# module_tester-v01.net
KiCad netlist of a schematic drawn in EAGLE
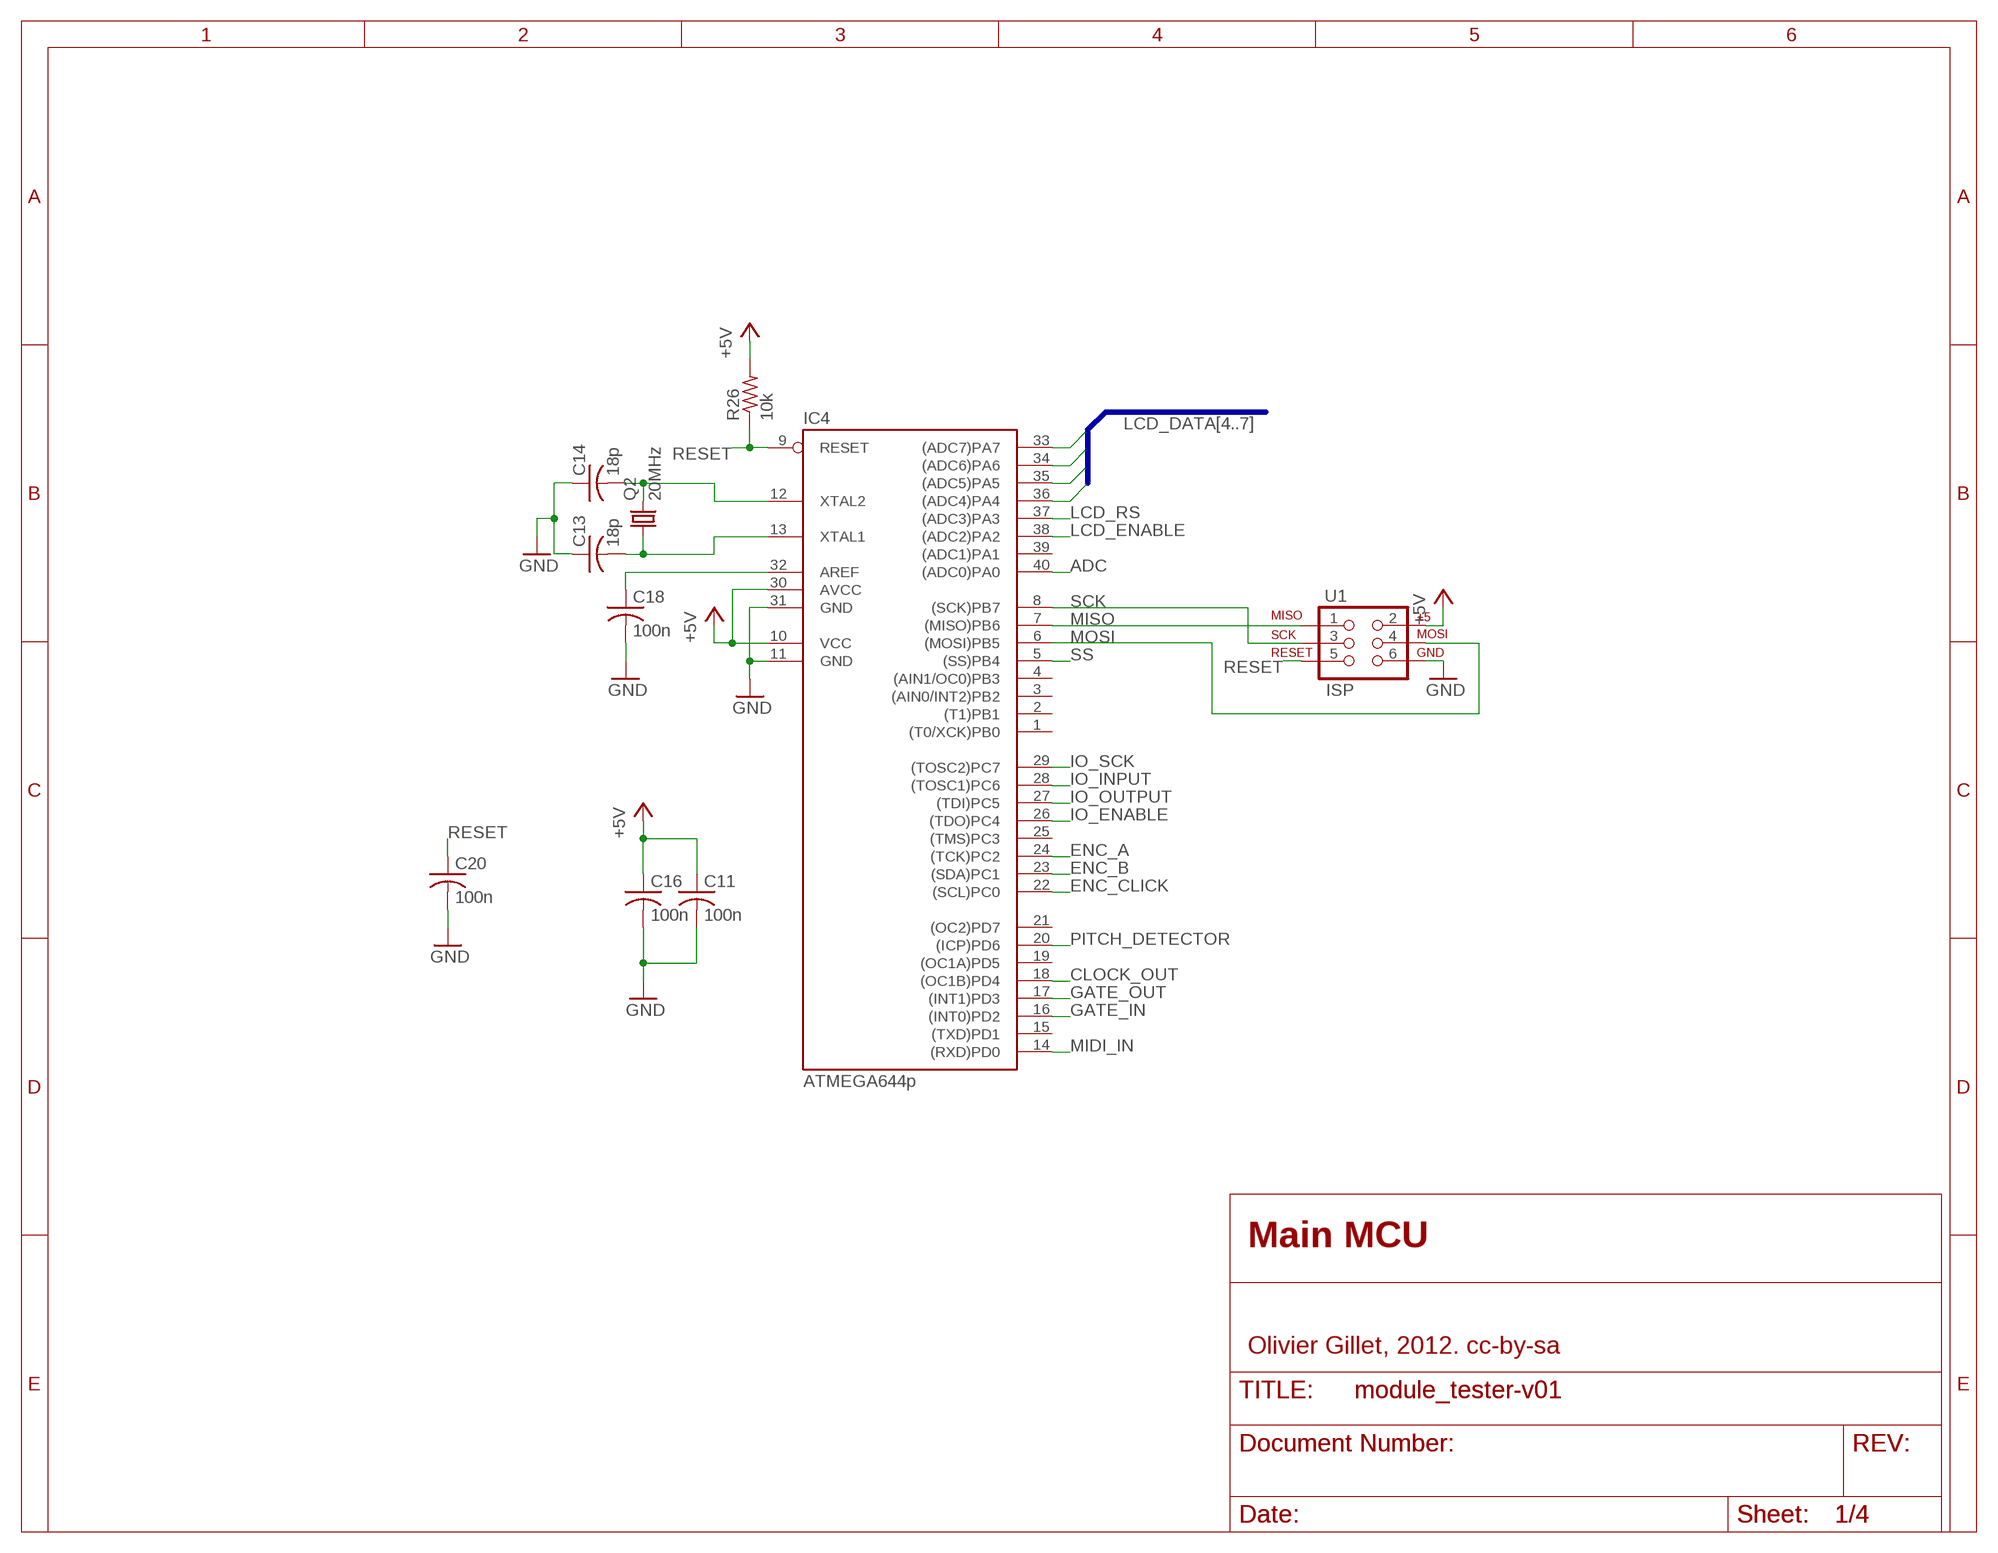
[diagram p0: schematic, sheet 1]
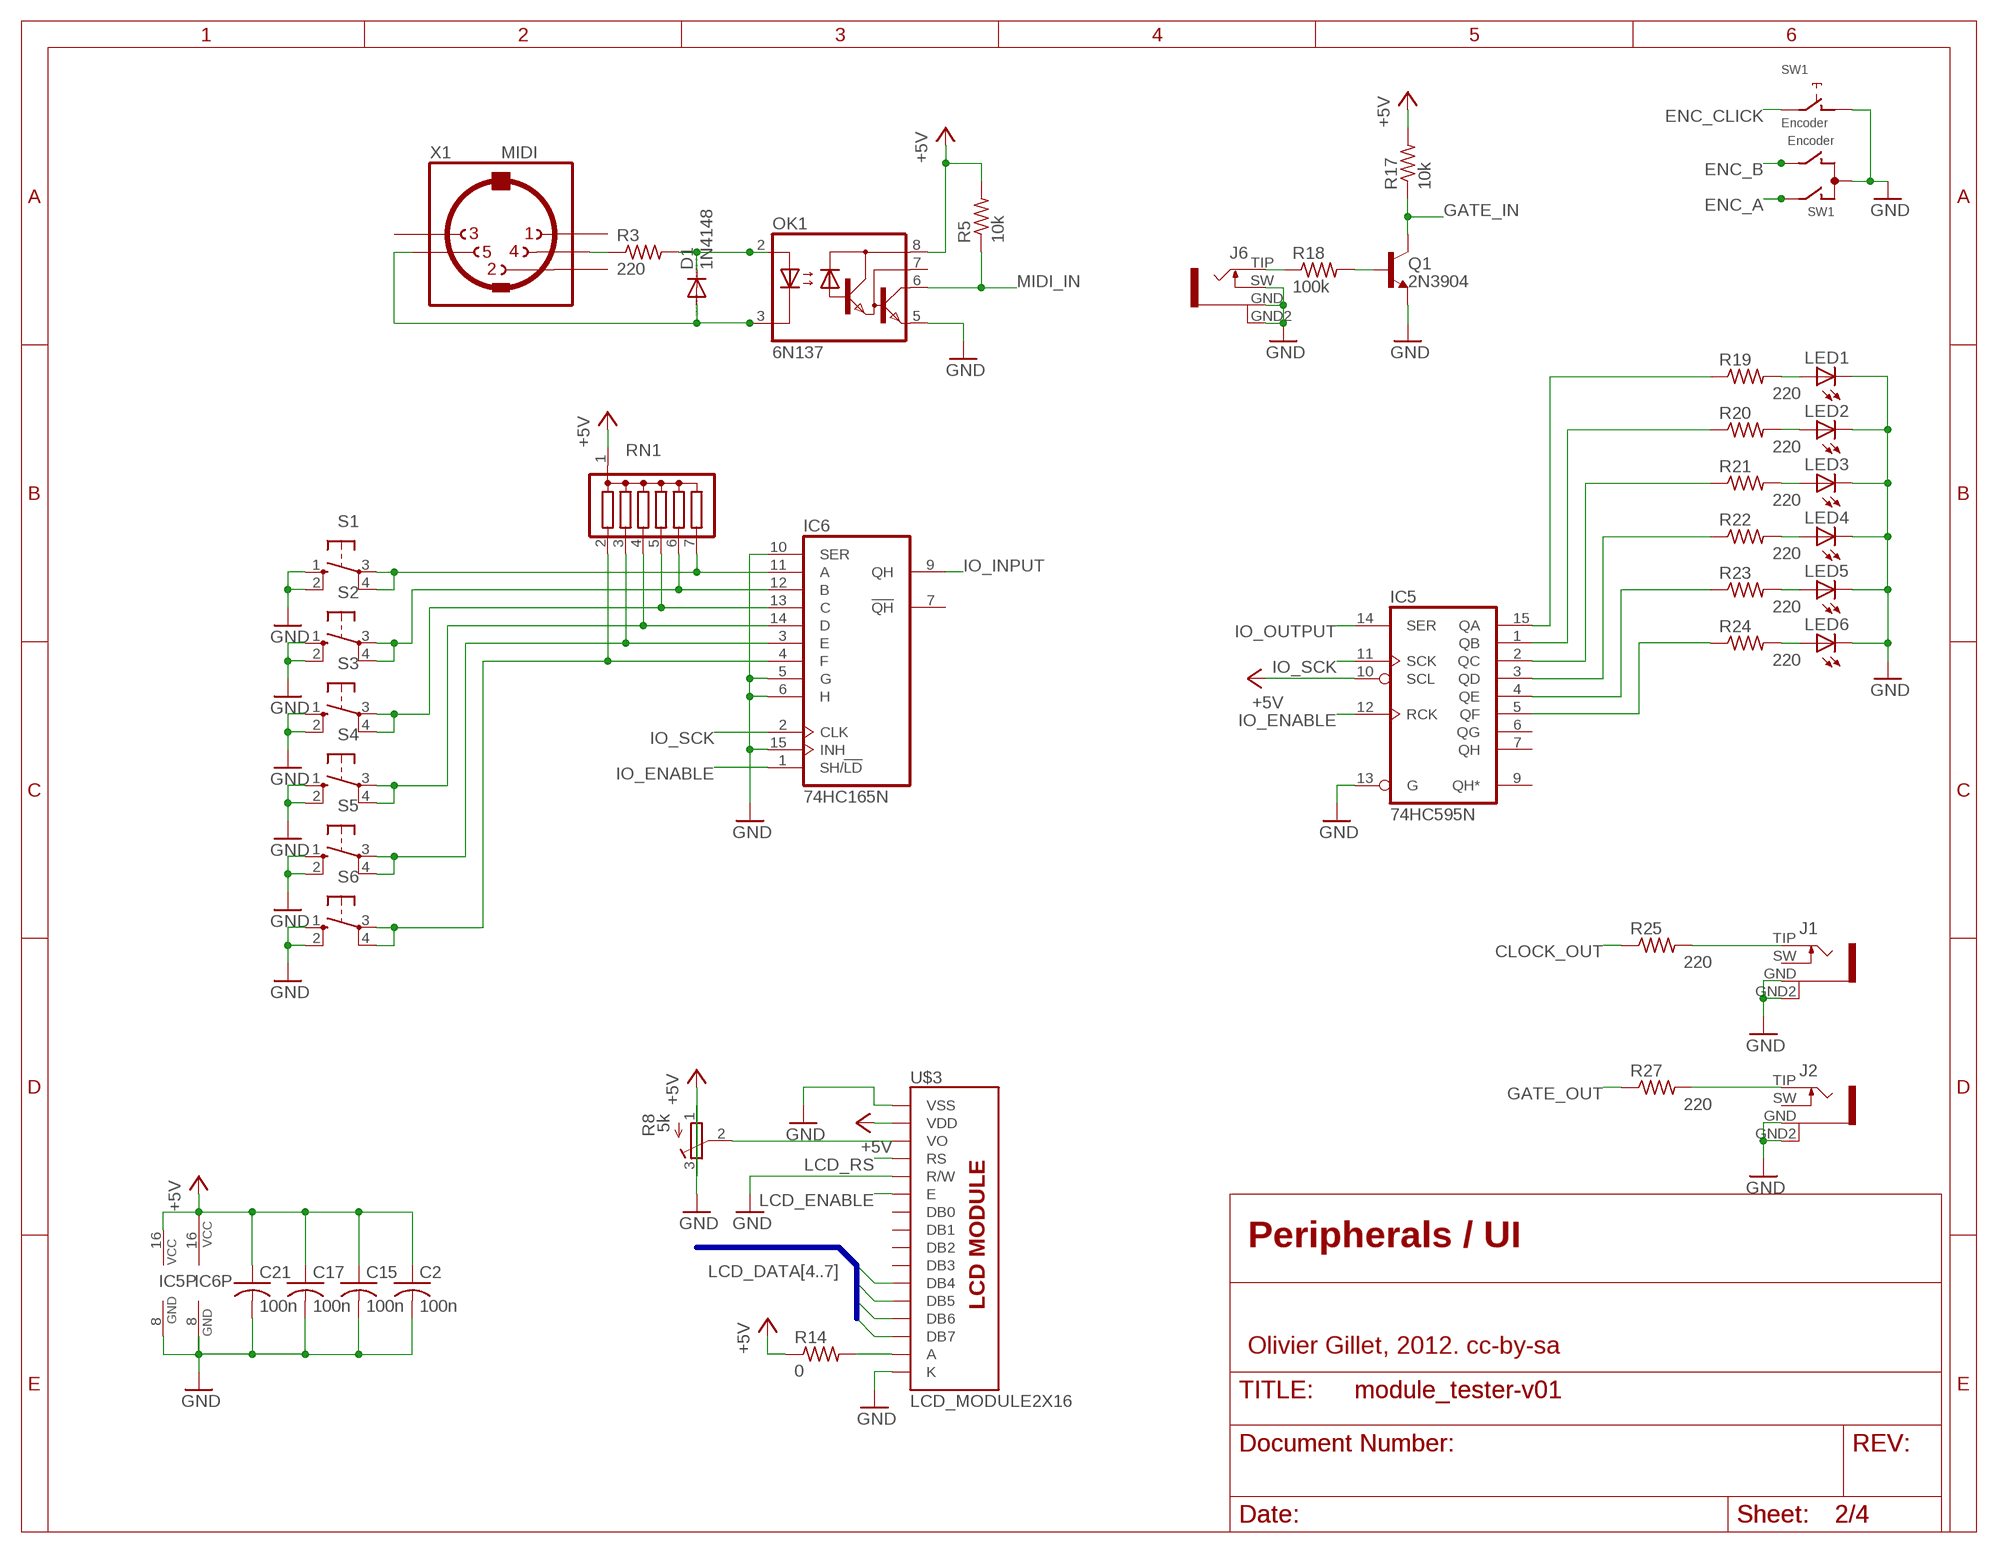
[diagram p1: schematic, sheet 2]
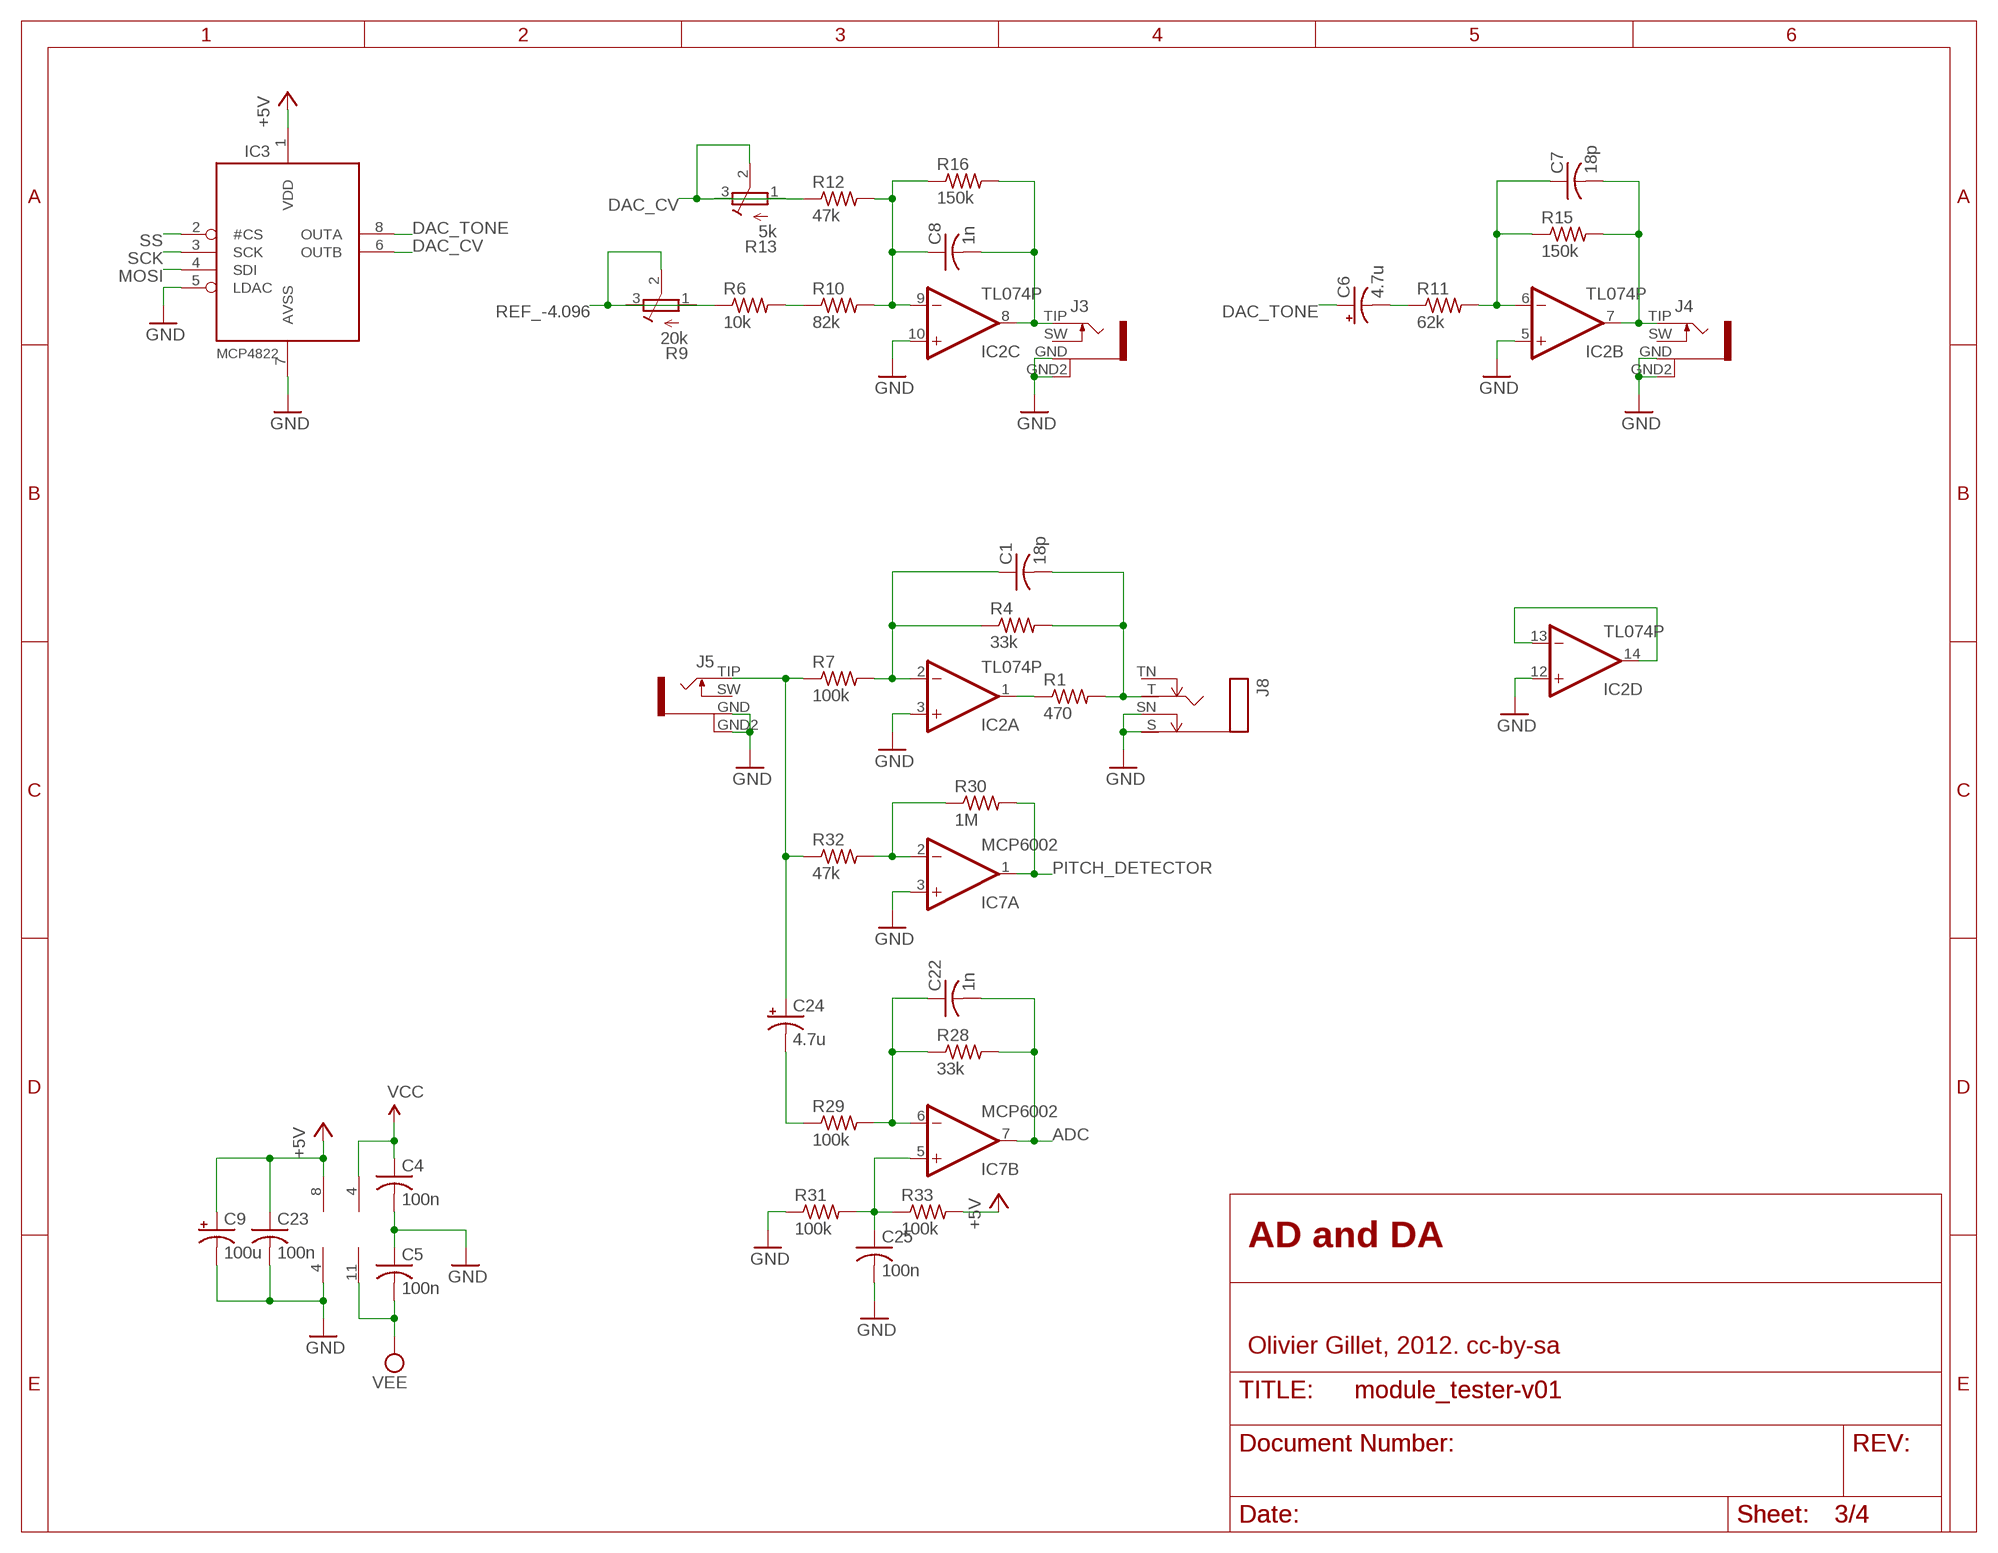
[diagram p2: schematic, sheet 3]
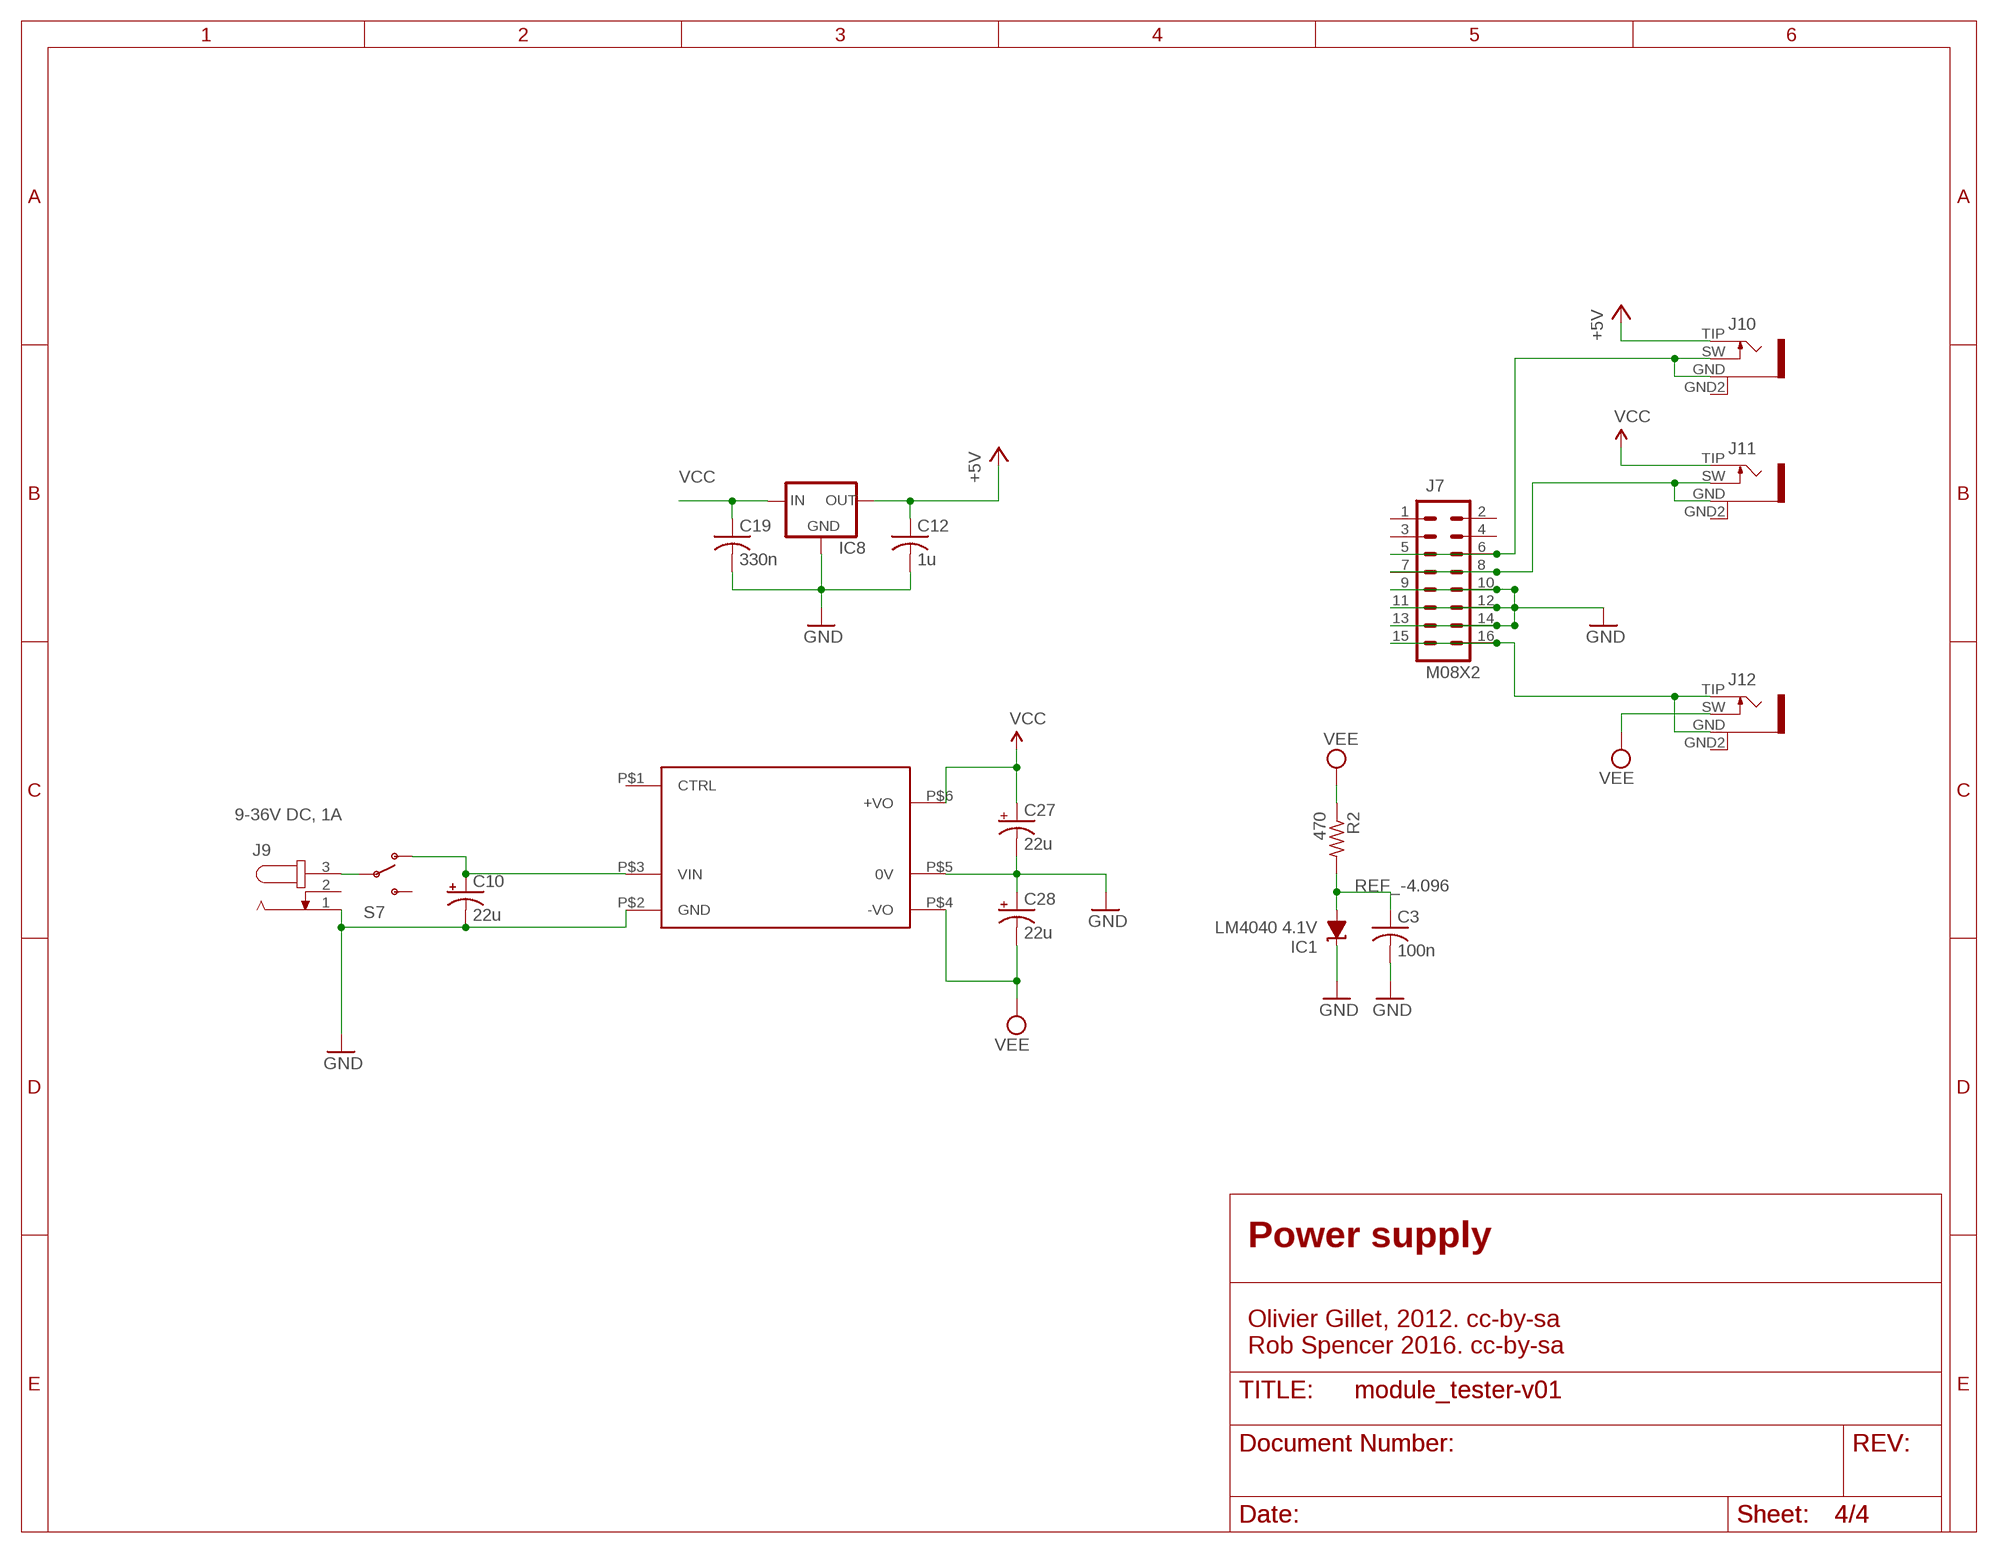
[diagram p3: schematic, sheet 4]

(export (version "E")
  (design (tool "Eeschema 10.0.6"))
  (components
    (comp (ref "C3")
      (value "100n")
      (footprint "eagle-import:C025-025X050")
      (libsource (lib "eagle-import") (part "C-US025-025X050"))
    )
    (comp (ref "C10")
      (value "22u")
      (footprint "eagle-import:E2,5-7")
      (libsource (lib "eagle-import") (part "CPOL-USE2.5-7"))
    )
    (comp (ref "C12")
      (value "1u")
      (footprint "eagle-import:C025-025X050")
      (libsource (lib "eagle-import") (part "C-US025-025X050"))
    )
    (comp (ref "C19")
      (value "330n")
      (footprint "eagle-import:C025-025X050")
      (libsource (lib "eagle-import") (part "C-US025-025X050"))
    )
    (comp (ref "C27")
      (value "22u")
      (footprint "eagle-import:E2,5-7")
      (libsource (lib "eagle-import") (part "CPOL-USE2.5-7"))
    )
    (comp (ref "C28")
      (value "22u")
      (footprint "eagle-import:E2,5-7")
      (libsource (lib "eagle-import") (part "CPOL-USE2.5-7"))
    )
    (comp (ref "IC1")
      (value "LM4040 4.1V")
      (footprint "eagle-import:LP_O-PBCY-W3")
      (fields (field (name "MPN") "LM4041C12ILP"))
      (libsource (lib "eagle-import") (part "LM4041LPC12"))
    )
    (comp (ref "IC8")
      (value "V_REG_78XX-TO-220")
      (footprint "eagle-import:TO-220-ALT")
      (libsource (lib "eagle-import") (part "V_REG_78XX-TO-220"))
    )
    (comp (ref "J7")
      (value "M08X2")
      (footprint "eagle-import:2X8")
      (libsource (lib "eagle-import") (part "M08X2"))
    )
    (comp (ref "J9")
      (value "JACK-PLUG2")
      (footprint "eagle-import:SPC4078_BIG_HOLES")
      (libsource (lib "eagle-import") (part "JACK-PLUG2"))
    )
    (comp (ref "J10")
      (value "PJ301WQP")
      (footprint "eagle-import:WQP_PJ_301BM")
      (libsource (lib "eagle-import") (part "PJ301WQP"))
    )
    (comp (ref "J11")
      (value "PJ301WQP")
      (footprint "eagle-import:WQP_PJ_301BM")
      (libsource (lib "eagle-import") (part "PJ301WQP"))
    )
    (comp (ref "J12")
      (value "PJ301WQP")
      (footprint "eagle-import:WQP_PJ_301BM")
      (libsource (lib "eagle-import") (part "PJ301WQP"))
    )
    (comp (ref "R2")
      (value "470")
      (footprint "eagle-import:0204_7")
      (libsource (lib "eagle-import") (part "resistor_R-US_0204/7"))
    )
    (comp (ref "S7")
      (value "SWITCH-SPDTPTH")
      (footprint "eagle-import:SWITCH-SPDT")
      (libsource (lib "eagle-import") (part "SWITCH-SPDTPTH"))
    )
    (comp (ref "U$10")
      (value "URA241XLD-20WR3")
      (footprint "eagle-import:URA241XLD-20WR3")
      (libsource (lib "eagle-import") (part "URA241XLD-20WR3"))
    )
    (comp (ref "C1")
      (value "18p")
      (footprint "eagle-import:C025-025X050")
      (libsource (lib "eagle-import") (part "C-US025-025X050"))
    )
    (comp (ref "C4")
      (value "100n")
      (footprint "eagle-import:C025-025X050")
      (libsource (lib "eagle-import") (part "C-US025-025X050"))
    )
    (comp (ref "C5")
      (value "100n")
      (footprint "eagle-import:C025-025X050")
      (libsource (lib "eagle-import") (part "C-US025-025X050"))
    )
    (comp (ref "C6")
      (value "4.7u")
      (footprint "eagle-import:E2,5-6")
      (libsource (lib "eagle-import") (part "CPOL-USE2.5-6"))
    )
    (comp (ref "C7")
      (value "18p")
      (footprint "eagle-import:C025-025X050")
      (libsource (lib "eagle-import") (part "C-US025-025X050"))
    )
    (comp (ref "C8")
      (value "1n")
      (footprint "eagle-import:C025-025X050")
      (libsource (lib "eagle-import") (part "C-US025-025X050"))
    )
    (comp (ref "C9")
      (value "100u")
      (footprint "eagle-import:E2,5-7")
      (libsource (lib "eagle-import") (part "CPOL-USE2.5-7"))
    )
    (comp (ref "C22")
      (value "1n")
      (footprint "eagle-import:C025-025X050")
      (libsource (lib "eagle-import") (part "C-US025-025X050"))
    )
    (comp (ref "C23")
      (value "100n")
      (footprint "eagle-import:C025-025X050")
      (libsource (lib "eagle-import") (part "C-US025-025X050"))
    )
    (comp (ref "C24")
      (value "4.7u")
      (footprint "eagle-import:E2,5-6")
      (libsource (lib "eagle-import") (part "CPOL-USE2.5-6"))
    )
    (comp (ref "C25")
      (value "100n")
      (footprint "eagle-import:C025-025X050")
      (libsource (lib "eagle-import") (part "C-US025-025X050"))
    )
    (comp (ref "IC2")
      (value "TL074P")
      (footprint "eagle-import:DIL14")
      (libsource (lib "eagle-import") (part "TL074P"))
    )
    (comp (ref "IC3")
      (value "MCP4822")
      (footprint "eagle-import:DIL08")
      (libsource (lib "eagle-import") (part "MCP4822"))
    )
    (comp (ref "IC7")
      (value "MCP6002")
      (footprint "eagle-import:DIL08")
      (libsource (lib "eagle-import") (part "TL072P"))
    )
    (comp (ref "J3")
      (value "PJ301WQP")
      (footprint "eagle-import:WQP_PJ_301BM")
      (libsource (lib "eagle-import") (part "PJ301WQP"))
    )
    (comp (ref "J4")
      (value "PJ301WQP")
      (footprint "eagle-import:WQP_PJ_301BM")
      (libsource (lib "eagle-import") (part "PJ301WQP"))
    )
    (comp (ref "J5")
      (value "PJ301WQP")
      (footprint "eagle-import:WQP_PJ_301BM")
      (libsource (lib "eagle-import") (part "PJ301WQP"))
    )
    (comp (ref "J8")
      (value "MONOSWSLIM")
      (footprint "eagle-import:NRJ4HF")
      (libsource (lib "eagle-import") (part "MONOSWSLIM"))
    )
    (comp (ref "R1")
      (value "470")
      (footprint "eagle-import:0204_7")
      (libsource (lib "eagle-import") (part "R-US_0204/7"))
    )
    (comp (ref "R4")
      (value "33k")
      (footprint "eagle-import:0204_7")
      (libsource (lib "eagle-import") (part "R-US_0204/7"))
    )
    (comp (ref "R6")
      (value "10k")
      (footprint "eagle-import:0204_7")
      (libsource (lib "eagle-import") (part "R-US_0204/7"))
    )
    (comp (ref "R7")
      (value "100k")
      (footprint "eagle-import:0204_7")
      (libsource (lib "eagle-import") (part "R-US_0204/7"))
    )
    (comp (ref "R9")
      (value "20k")
      (footprint "eagle-import:RTRIM3296W")
      (libsource (lib "eagle-import") (part "R-TRIMM3296W"))
    )
    (comp (ref "R10")
      (value "82k")
      (footprint "eagle-import:0204_7")
      (libsource (lib "eagle-import") (part "R-US_0204/7"))
    )
    (comp (ref "R11")
      (value "62k")
      (footprint "eagle-import:0204_7")
      (libsource (lib "eagle-import") (part "R-US_0204/7"))
    )
    (comp (ref "R12")
      (value "47k")
      (footprint "eagle-import:0204_7")
      (libsource (lib "eagle-import") (part "R-US_0204/7"))
    )
    (comp (ref "R13")
      (value "5k")
      (footprint "eagle-import:RTRIM3296W")
      (libsource (lib "eagle-import") (part "R-TRIMM3296W"))
    )
    (comp (ref "R15")
      (value "150k")
      (footprint "eagle-import:0204_7")
      (libsource (lib "eagle-import") (part "R-US_0204/7"))
    )
    (comp (ref "R16")
      (value "150k")
      (footprint "eagle-import:0204_7")
      (libsource (lib "eagle-import") (part "R-US_0204/7"))
    )
    (comp (ref "R28")
      (value "33k")
      (footprint "eagle-import:0204_7")
      (libsource (lib "eagle-import") (part "R-US_0204/7"))
    )
    (comp (ref "R29")
      (value "100k")
      (footprint "eagle-import:0204_7")
      (libsource (lib "eagle-import") (part "R-US_0204/7"))
    )
    (comp (ref "R30")
      (value "1M")
      (footprint "eagle-import:0204_7")
      (libsource (lib "eagle-import") (part "R-US_0204/7"))
    )
    (comp (ref "R31")
      (value "100k")
      (footprint "eagle-import:0204_7")
      (libsource (lib "eagle-import") (part "R-US_0204/7"))
    )
    (comp (ref "R32")
      (value "47k")
      (footprint "eagle-import:0204_7")
      (libsource (lib "eagle-import") (part "R-US_0204/7"))
    )
    (comp (ref "R33")
      (value "100k")
      (footprint "eagle-import:0204_7")
      (libsource (lib "eagle-import") (part "R-US_0204/7"))
    )
    (comp (ref "C11")
      (value "100n")
      (footprint "eagle-import:C025-025X050")
      (libsource (lib "eagle-import") (part "C-US025-025X050"))
    )
    (comp (ref "C13")
      (value "18p")
      (footprint "eagle-import:C025-025X050")
      (libsource (lib "eagle-import") (part "C-US025-025X050"))
    )
    (comp (ref "C14")
      (value "18p")
      (footprint "eagle-import:C025-025X050")
      (libsource (lib "eagle-import") (part "C-US025-025X050"))
    )
    (comp (ref "C16")
      (value "100n")
      (footprint "eagle-import:C025-025X050")
      (libsource (lib "eagle-import") (part "C-US025-025X050"))
    )
    (comp (ref "C18")
      (value "100n")
      (footprint "eagle-import:C025-025X050")
      (libsource (lib "eagle-import") (part "C-US025-025X050"))
    )
    (comp (ref "C20")
      (value "100n")
      (footprint "eagle-import:C025-025X050")
      (libsource (lib "eagle-import") (part "C-US025-025X050"))
    )
    (comp (ref "IC4")
      (value "ATMEGA644p")
      (footprint "eagle-import:DIL40")
      (fields (field (name "MPN") "ATMEGA16-16PU"))
      (libsource (lib "eagle-import") (part "MEGA16-P"))
    )
    (comp (ref "Q2")
      (value "20MHz")
      (footprint "eagle-import:HC49U-V")
      (libsource (lib "eagle-import") (part "CRYSTALHC49U-V"))
    )
    (comp (ref "R26")
      (value "10k")
      (footprint "eagle-import:0204_7")
      (libsource (lib "eagle-import") (part "R-US_0204/7"))
    )
    (comp (ref "U1")
      (value "ISP")
      (footprint "eagle-import:2X3")
      (libsource (lib "eagle-import") (part "AVR_SPI_PRG_6PTH"))
    )
    (comp (ref "C2")
      (value "100n")
      (footprint "eagle-import:C025-025X050")
      (libsource (lib "eagle-import") (part "C-US025-025X050"))
    )
    (comp (ref "C15")
      (value "100n")
      (footprint "eagle-import:C025-025X050")
      (libsource (lib "eagle-import") (part "C-US025-025X050"))
    )
    (comp (ref "C17")
      (value "100n")
      (footprint "eagle-import:C025-025X050")
      (libsource (lib "eagle-import") (part "C-US025-025X050"))
    )
    (comp (ref "C21")
      (value "100n")
      (footprint "eagle-import:C025-025X050")
      (libsource (lib "eagle-import") (part "C-US025-025X050"))
    )
    (comp (ref "D1")
      (value "1N4148")
      (footprint "eagle-import:D-5")
      (libsource (lib "eagle-import") (part "DIODE-D-5"))
    )
    (comp (ref "IC5")
      (value "74HC595N")
      (footprint "eagle-import:DIL16")
      (libsource (lib "eagle-import") (part "74595NHC"))
    )
    (comp (ref "IC6")
      (value "74HC165N")
      (footprint "eagle-import:DIL16")
      (libsource (lib "eagle-import") (part "74165NLS"))
    )
    (comp (ref "J1")
      (value "PJ301WQP")
      (footprint "eagle-import:WQP_PJ_301BM")
      (libsource (lib "eagle-import") (part "PJ301WQP"))
    )
    (comp (ref "J2")
      (value "PJ301WQP")
      (footprint "eagle-import:WQP_PJ_301BM")
      (libsource (lib "eagle-import") (part "PJ301WQP"))
    )
    (comp (ref "J6")
      (value "PJ301WQP")
      (footprint "eagle-import:WQP_PJ_301BM")
      (libsource (lib "eagle-import") (part "PJ301WQP"))
    )
    (comp (ref "LED1")
      (value "LED3MM")
      (footprint "eagle-import:LED3MM")
      (libsource (lib "eagle-import") (part "LED3MM"))
    )
    (comp (ref "LED2")
      (value "LED3MM")
      (footprint "eagle-import:LED3MM")
      (libsource (lib "eagle-import") (part "LED3MM"))
    )
    (comp (ref "LED3")
      (value "LED3MM")
      (footprint "eagle-import:LED3MM")
      (libsource (lib "eagle-import") (part "LED3MM"))
    )
    (comp (ref "LED4")
      (value "LED3MM")
      (footprint "eagle-import:LED3MM")
      (libsource (lib "eagle-import") (part "LED3MM"))
    )
    (comp (ref "LED5")
      (value "LED3MM")
      (footprint "eagle-import:LED3MM")
      (libsource (lib "eagle-import") (part "LED3MM"))
    )
    (comp (ref "LED6")
      (value "LED3MM")
      (footprint "eagle-import:LED3MM")
      (libsource (lib "eagle-import") (part "LED3MM"))
    )
    (comp (ref "OK1")
      (value "6N137")
      (footprint "eagle-import:DIL08")
      (fields (field (name "MF") "VISHAY/TELEFUNKEN") (field (name "MPN") "6N138"))
      (libsource (lib "eagle-import") (part "6N138"))
    )
    (comp (ref "Q1")
      (value "2N3904")
      (footprint "eagle-import:TO92-")
      (libsource (lib "eagle-import") (part "2N3904"))
    )
    (comp (ref "R3")
      (value "220")
      (footprint "eagle-import:0204_7")
      (libsource (lib "eagle-import") (part "R-US_0204/7"))
    )
    (comp (ref "R5")
      (value "10k")
      (footprint "eagle-import:0204_7")
      (libsource (lib "eagle-import") (part "R-US_0204/7"))
    )
    (comp (ref "R8")
      (value "5k")
      (footprint "eagle-import:RTRIM3296W")
      (libsource (lib "eagle-import") (part "resistor_R-TRIMM3296W"))
    )
    (comp (ref "R14")
      (value "0")
      (footprint "eagle-import:0204_7")
      (libsource (lib "eagle-import") (part "R-US_0204/7"))
    )
    (comp (ref "R17")
      (value "10k")
      (footprint "eagle-import:0204_7")
      (libsource (lib "eagle-import") (part "R-US_0204/7"))
    )
    (comp (ref "R18")
      (value "100k")
      (footprint "eagle-import:0204_7")
      (libsource (lib "eagle-import") (part "R-US_0204/7"))
    )
    (comp (ref "R19")
      (value "220")
      (footprint "eagle-import:0204_7")
      (libsource (lib "eagle-import") (part "R-US_0204/7"))
    )
    (comp (ref "R20")
      (value "220")
      (footprint "eagle-import:0204_7")
      (libsource (lib "eagle-import") (part "R-US_0204/7"))
    )
    (comp (ref "R21")
      (value "220")
      (footprint "eagle-import:0204_7")
      (libsource (lib "eagle-import") (part "R-US_0204/7"))
    )
    (comp (ref "R22")
      (value "220")
      (footprint "eagle-import:0204_7")
      (libsource (lib "eagle-import") (part "R-US_0204/7"))
    )
    (comp (ref "R23")
      (value "220")
      (footprint "eagle-import:0204_7")
      (libsource (lib "eagle-import") (part "R-US_0204/7"))
    )
    (comp (ref "R24")
      (value "220")
      (footprint "eagle-import:0204_7")
      (libsource (lib "eagle-import") (part "R-US_0204/7"))
    )
    (comp (ref "R25")
      (value "220")
      (footprint "eagle-import:0204_7")
      (libsource (lib "eagle-import") (part "R-US_0204/7"))
    )
    (comp (ref "R27")
      (value "220")
      (footprint "eagle-import:0204_7")
      (libsource (lib "eagle-import") (part "R-US_0204/7"))
    )
    (comp (ref "RN1")
      (value "G06R")
      (footprint "eagle-import:SIL7")
      (libsource (lib "eagle-import") (part "G06R"))
    )
    (comp (ref "S1")
      (value "40-XX")
      (footprint "eagle-import:B3F-40XX")
      (libsource (lib "eagle-import") (part "40-XX"))
    )
    (comp (ref "S2")
      (value "40-XX")
      (footprint "eagle-import:B3F-40XX")
      (libsource (lib "eagle-import") (part "40-XX"))
    )
    (comp (ref "S3")
      (value "40-XX")
      (footprint "eagle-import:B3F-40XX")
      (libsource (lib "eagle-import") (part "40-XX"))
    )
    (comp (ref "S4")
      (value "40-XX")
      (footprint "eagle-import:B3F-40XX")
      (libsource (lib "eagle-import") (part "40-XX"))
    )
    (comp (ref "S5")
      (value "40-XX")
      (footprint "eagle-import:B3F-40XX")
      (libsource (lib "eagle-import") (part "40-XX"))
    )
    (comp (ref "S6")
      (value "40-XX")
      (footprint "eagle-import:B3F-40XX")
      (libsource (lib "eagle-import") (part "40-XX"))
    )
    (comp (ref "SW1")
      (value "Encoder")
      (footprint "eagle-import:ALPS_EC12E_SW")
      (fields (field (name "MPN") "EC12E2424407"))
      (libsource (lib "eagle-import") (part "EC12E_SW"))
    )
    (comp (ref "U$3")
      (value "LCD_MODULE2X16")
      (footprint "eagle-import:LCD_MODULE_2X16")
      (libsource (lib "eagle-import") (part "LCD_MODULE2X16"))
    )
    (comp (ref "X1")
      (value "MIDI")
      (footprint "eagle-import:MAB5SH")
      (libsource (lib "eagle-import") (part "MAB5SH"))
    )
  )
  (nets
    (net (code "1") (name "+5V") (class "Default")
      (node (ref "C11") (pin "1") (pinfunction "1_1") (pintype "passive"))
      (node (ref "C12") (pin "1") (pinfunction "1_1") (pintype "passive"))
      (node (ref "C15") (pin "1") (pinfunction "1_1") (pintype "passive"))
      (node (ref "C16") (pin "1") (pinfunction "1_1") (pintype "passive"))
      (node (ref "C17") (pin "1") (pinfunction "1_1") (pintype "passive"))
      (node (ref "C2") (pin "1") (pinfunction "1_1") (pintype "passive"))
      (node (ref "C21") (pin "1") (pinfunction "1_1") (pintype "passive"))
      (node (ref "C23") (pin "1") (pinfunction "1_1") (pintype "passive"))
      (node (ref "C9") (pin "+") (pinfunction "+_+") (pintype "passive"))
      (node (ref "IC3") (pin "1") (pinfunction "VDD_1") (pintype "power_in"))
      (node (ref "IC4") (pin "10") (pinfunction "VCC_10") (pintype "power_in"))
      (node (ref "IC4") (pin "30") (pinfunction "AVCC_30") (pintype "power_in"))
      (node (ref "IC5") (pin "10") (pinfunction "SCL_10") (pintype "input"))
      (node (ref "IC5") (pin "16") (pinfunction "VCC_16") (pintype "power_in"))
      (node (ref "IC6") (pin "16") (pinfunction "VCC_16") (pintype "power_in"))
      (node (ref "IC7") (pin "8") (pinfunction "V+_8") (pintype "power_in"))
      (node (ref "IC8") (pin "OUT") (pinfunction "OUT_OUT") (pintype "output"))
      (node (ref "J10") (pin "TIP") (pinfunction "2_TIP") (pintype "passive"))
      (node (ref "OK1") (pin "8") (pinfunction "VCC_8") (pintype "passive"))
      (node (ref "R14") (pin "1") (pinfunction "1_1") (pintype "passive"))
      (node (ref "R17") (pin "2") (pinfunction "2_2") (pintype "passive"))
      (node (ref "R26") (pin "2") (pinfunction "2_2") (pintype "passive"))
      (node (ref "R33") (pin "2") (pinfunction "2_2") (pintype "passive"))
      (node (ref "R5") (pin "2") (pinfunction "2_2") (pintype "passive"))
      (node (ref "R8") (pin "3") (pinfunction "E_3") (pintype "passive"))
      (node (ref "RN1") (pin "1") (pinfunction "1_1") (pintype "passive"))
      (node (ref "U$3") (pin "2") (pinfunction "VDD_2") (pintype "power_in"))
      (node (ref "U1") (pin "2") (pinfunction "2_2") (pintype "passive"))
    )
    (net (code "4") (name "ADC") (class "Default")
      (node (ref "C22") (pin "2") (pinfunction "2_2") (pintype "passive"))
      (node (ref "IC4") (pin "40") (pinfunction "(ADC0)PA0_40") (pintype "bidirectional"))
      (node (ref "IC7") (pin "7") (pinfunction "OUT_7") (pintype "output"))
      (node (ref "R28") (pin "2") (pinfunction "2_2") (pintype "passive"))
    )
    (net (code "5") (name "CLOCK_OUT") (class "Default")
      (node (ref "IC4") (pin "18") (pinfunction "(OC1B)PD4_18") (pintype "bidirectional"))
      (node (ref "R25") (pin "1") (pinfunction "1_1") (pintype "passive"))
    )
    (net (code "6") (name "DAC_CV") (class "Default")
      (node (ref "IC3") (pin "6") (pinfunction "OUTB_6") (pintype "output"))
      (node (ref "R13") (pin "1") (pinfunction "A_1") (pintype "passive"))
      (node (ref "R13") (pin "2") (pinfunction "S_2") (pintype "passive"))
    )
    (net (code "7") (name "DAC_TONE") (class "Default")
      (node (ref "C6") (pin "+") (pinfunction "+_+") (pintype "passive"))
      (node (ref "IC3") (pin "8") (pinfunction "OUTA_8") (pintype "output"))
    )
    (net (code "8") (name "ENC_A") (class "Default")
      (node (ref "IC4") (pin "24") (pinfunction "(TCK)PC2_24") (pintype "bidirectional"))
      (node (ref "SW1") (pin "A") (pinfunction "A_A") (pintype "passive"))
    )
    (net (code "9") (name "ENC_B") (class "Default")
      (node (ref "IC4") (pin "23") (pinfunction "(SDA)PC1_23") (pintype "bidirectional"))
      (node (ref "SW1") (pin "B") (pinfunction "B_B") (pintype "passive"))
    )
    (net (code "10") (name "ENC_CLICK") (class "Default")
      (node (ref "IC4") (pin "22") (pinfunction "(SCL)PC0_22") (pintype "bidirectional"))
      (node (ref "SW1") (pin "E") (pinfunction "2_E") (pintype "passive"))
    )
    (net (code "11") (name "GATE_IN") (class "Default")
      (node (ref "IC4") (pin "16") (pinfunction "(INT0)PD2_16") (pintype "bidirectional"))
      (node (ref "Q1") (pin "1") (pinfunction "C_1") (pintype "passive"))
      (node (ref "R17") (pin "1") (pinfunction "1_1") (pintype "passive"))
    )
    (net (code "12") (name "GATE_OUT") (class "Default")
      (node (ref "IC4") (pin "17") (pinfunction "(INT1)PD3_17") (pintype "bidirectional"))
      (node (ref "R27") (pin "1") (pinfunction "1_1") (pintype "passive"))
    )
    (net (code "13") (name "GND") (class "Default")
      (node (ref "C10") (pin "-") (pinfunction "-_-") (pintype "passive"))
      (node (ref "C11") (pin "2") (pinfunction "2_2") (pintype "passive"))
      (node (ref "C12") (pin "2") (pinfunction "2_2") (pintype "passive"))
      (node (ref "C13") (pin "1") (pinfunction "1_1") (pintype "passive"))
      (node (ref "C14") (pin "1") (pinfunction "1_1") (pintype "passive"))
      (node (ref "C15") (pin "2") (pinfunction "2_2") (pintype "passive"))
      (node (ref "C16") (pin "2") (pinfunction "2_2") (pintype "passive"))
      (node (ref "C17") (pin "2") (pinfunction "2_2") (pintype "passive"))
      (node (ref "C18") (pin "2") (pinfunction "2_2") (pintype "passive"))
      (node (ref "C19") (pin "2") (pinfunction "2_2") (pintype "passive"))
      (node (ref "C2") (pin "2") (pinfunction "2_2") (pintype "passive"))
      (node (ref "C20") (pin "2") (pinfunction "2_2") (pintype "passive"))
      (node (ref "C21") (pin "2") (pinfunction "2_2") (pintype "passive"))
      (node (ref "C23") (pin "2") (pinfunction "2_2") (pintype "passive"))
      (node (ref "C25") (pin "2") (pinfunction "2_2") (pintype "passive"))
      (node (ref "C27") (pin "-") (pinfunction "-_-") (pintype "passive"))
      (node (ref "C28") (pin "+") (pinfunction "+_+") (pintype "passive"))
      (node (ref "C3") (pin "2") (pinfunction "2_2") (pintype "passive"))
      (node (ref "C4") (pin "2") (pinfunction "2_2") (pintype "passive"))
      (node (ref "C5") (pin "1") (pinfunction "1_1") (pintype "passive"))
      (node (ref "C9") (pin "-") (pinfunction "-_-") (pintype "passive"))
      (node (ref "IC1") (pin "2") (pinfunction "C_2") (pintype "passive"))
      (node (ref "IC2") (pin "10") (pinfunction "+IN_10") (pintype "input"))
      (node (ref "IC2") (pin "12") (pinfunction "+IN_12") (pintype "input"))
      (node (ref "IC2") (pin "3") (pinfunction "+IN_3") (pintype "input"))
      (node (ref "IC2") (pin "5") (pinfunction "+IN_5") (pintype "input"))
      (node (ref "IC3") (pin "5") (pinfunction "LDAC_5") (pintype "input"))
      (node (ref "IC3") (pin "7") (pinfunction "AVSS_7") (pintype "power_in"))
      (node (ref "IC4") (pin "11") (pinfunction "GND_11") (pintype "power_in"))
      (node (ref "IC4") (pin "31") (pinfunction "GND_31") (pintype "power_in"))
      (node (ref "IC5") (pin "13") (pinfunction "G_13") (pintype "input"))
      (node (ref "IC5") (pin "8") (pinfunction "GND_8") (pintype "power_in"))
      (node (ref "IC6") (pin "10") (pinfunction "SER_10") (pintype "input"))
      (node (ref "IC6") (pin "15") (pinfunction "INH_15") (pintype "input"))
      (node (ref "IC6") (pin "5") (pinfunction "G_5") (pintype "input"))
      (node (ref "IC6") (pin "6") (pinfunction "H_6") (pintype "input"))
      (node (ref "IC6") (pin "8") (pinfunction "GND_8") (pintype "power_in"))
      (node (ref "IC7") (pin "3") (pinfunction "+IN_3") (pintype "input"))
      (node (ref "IC7") (pin "4") (pinfunction "V-_4") (pintype "power_in"))
      (node (ref "IC8") (pin "GND") (pinfunction "GND_GND") (pintype "input"))
      (node (ref "J1") (pin "GND") (pinfunction "1_GND") (pintype "passive"))
      (node (ref "J1") (pin "GND2") (pinfunction "4_GND2") (pintype "passive"))
      (node (ref "J2") (pin "GND") (pinfunction "1_GND") (pintype "passive"))
      (node (ref "J2") (pin "GND2") (pinfunction "4_GND2") (pintype "passive"))
      (node (ref "J3") (pin "GND") (pinfunction "1_GND") (pintype "passive"))
      (node (ref "J3") (pin "GND2") (pinfunction "4_GND2") (pintype "passive"))
      (node (ref "J4") (pin "GND") (pinfunction "1_GND") (pintype "passive"))
      (node (ref "J4") (pin "GND2") (pinfunction "4_GND2") (pintype "passive"))
      (node (ref "J5") (pin "GND") (pinfunction "1_GND") (pintype "passive"))
      (node (ref "J5") (pin "GND2") (pinfunction "4_GND2") (pintype "passive"))
      (node (ref "J6") (pin "GND") (pinfunction "1_GND") (pintype "passive"))
      (node (ref "J6") (pin "GND2") (pinfunction "4_GND2") (pintype "passive"))
      (node (ref "J6") (pin "SW") (pinfunction "3_SW") (pintype "passive"))
      (node (ref "J7") (pin "10") (pinfunction "10_10") (pintype "passive"))
      (node (ref "J7") (pin "11") (pinfunction "11_11") (pintype "passive"))
      (node (ref "J7") (pin "12") (pinfunction "12_12") (pintype "passive"))
      (node (ref "J7") (pin "13") (pinfunction "13_13") (pintype "passive"))
      (node (ref "J7") (pin "14") (pinfunction "14_14") (pintype "passive"))
      (node (ref "J7") (pin "9") (pinfunction "9_9") (pintype "passive"))
      (node (ref "J8") (pin "S") (pinfunction "S_S") (pintype "passive"))
      (node (ref "J8") (pin "SN") (pinfunction "SN_SN") (pintype "passive"))
      (node (ref "J9") (pin "1") (pinfunction "1_1") (pintype "passive"))
      (node (ref "LED1") (pin "K") (pinfunction "C_K") (pintype "passive"))
      (node (ref "LED2") (pin "K") (pinfunction "C_K") (pintype "passive"))
      (node (ref "LED3") (pin "K") (pinfunction "C_K") (pintype "passive"))
      (node (ref "LED4") (pin "K") (pinfunction "C_K") (pintype "passive"))
      (node (ref "LED5") (pin "K") (pinfunction "C_K") (pintype "passive"))
      (node (ref "LED6") (pin "K") (pinfunction "C_K") (pintype "passive"))
      (node (ref "OK1") (pin "5") (pinfunction "GND_5") (pintype "passive"))
      (node (ref "Q1") (pin "3") (pinfunction "E_3") (pintype "passive"))
      (node (ref "R31") (pin "1") (pinfunction "1_1") (pintype "passive"))
      (node (ref "R8") (pin "1") (pinfunction "A_1") (pintype "passive"))
      (node (ref "S1") (pin "1") (pinfunction "S_1") (pintype "passive"))
      (node (ref "S1") (pin "2") (pinfunction "S1_2") (pintype "passive"))
      (node (ref "S2") (pin "1") (pinfunction "S_1") (pintype "passive"))
      (node (ref "S2") (pin "2") (pinfunction "S1_2") (pintype "passive"))
      (node (ref "S3") (pin "1") (pinfunction "S_1") (pintype "passive"))
      (node (ref "S3") (pin "2") (pinfunction "S1_2") (pintype "passive"))
      (node (ref "S4") (pin "1") (pinfunction "S_1") (pintype "passive"))
      (node (ref "S4") (pin "2") (pinfunction "S1_2") (pintype "passive"))
      (node (ref "S5") (pin "1") (pinfunction "S_1") (pintype "passive"))
      (node (ref "S5") (pin "2") (pinfunction "S1_2") (pintype "passive"))
      (node (ref "S6") (pin "1") (pinfunction "S_1") (pintype "passive"))
      (node (ref "S6") (pin "2") (pinfunction "S1_2") (pintype "passive"))
      (node (ref "SW1") (pin "C") (pinfunction "C_C") (pintype "passive"))
      (node (ref "SW1") (pin "D") (pinfunction "1_D") (pintype "passive"))
      (node (ref "U$10") (pin "P$2") (pinfunction "GND_P$2") (pintype "bidirectional"))
      (node (ref "U$10") (pin "P$5") (pinfunction "0V_P$5") (pintype "bidirectional"))
      (node (ref "U$3") (pin "1") (pinfunction "VSS_1") (pintype "power_in"))
      (node (ref "U$3") (pin "16") (pinfunction "K_16") (pintype "power_in"))
      (node (ref "U$3") (pin "5") (pinfunction "R/W_5") (pintype "input"))
      (node (ref "U1") (pin "6") (pinfunction "6_6") (pintype "passive"))
    )
    (net (code "14") (name "IO_ENABLE") (class "Default")
      (node (ref "IC4") (pin "26") (pinfunction "(TDO)PC4_26") (pintype "bidirectional"))
      (node (ref "IC5") (pin "12") (pinfunction "RCK_12") (pintype "input"))
      (node (ref "IC6") (pin "1") (pinfunction "SH/~{LD}_1") (pintype "input"))
    )
    (net (code "15") (name "IO_INPUT") (class "Default")
      (node (ref "IC4") (pin "28") (pinfunction "(TOSC1)PC6_28") (pintype "bidirectional"))
      (node (ref "IC6") (pin "9") (pinfunction "QH_9") (pintype "output"))
    )
    (net (code "16") (name "IO_OUTPUT") (class "Default")
      (node (ref "IC4") (pin "27") (pinfunction "(TDI)PC5_27") (pintype "bidirectional"))
      (node (ref "IC5") (pin "14") (pinfunction "SER_14") (pintype "input"))
    )
    (net (code "17") (name "IO_SCK") (class "Default")
      (node (ref "IC4") (pin "29") (pinfunction "(TOSC2)PC7_29") (pintype "bidirectional"))
      (node (ref "IC5") (pin "11") (pinfunction "SCK_11") (pintype "input"))
      (node (ref "IC6") (pin "2") (pinfunction "CLK_2") (pintype "input"))
    )
    (net (code "18") (name "LCD_DATA4") (class "Default")
      (node (ref "IC4") (pin "36") (pinfunction "(ADC4)PA4_36") (pintype "bidirectional"))
      (node (ref "U$3") (pin "11") (pinfunction "DB4_11") (pintype "bidirectional"))
    )
    (net (code "19") (name "LCD_DATA5") (class "Default")
      (node (ref "IC4") (pin "35") (pinfunction "(ADC5)PA5_35") (pintype "bidirectional"))
      (node (ref "U$3") (pin "12") (pinfunction "DB5_12") (pintype "bidirectional"))
    )
    (net (code "20") (name "LCD_DATA6") (class "Default")
      (node (ref "IC4") (pin "34") (pinfunction "(ADC6)PA6_34") (pintype "bidirectional"))
      (node (ref "U$3") (pin "13") (pinfunction "DB6_13") (pintype "bidirectional"))
    )
    (net (code "21") (name "LCD_DATA7") (class "Default")
      (node (ref "IC4") (pin "33") (pinfunction "(ADC7)PA7_33") (pintype "bidirectional"))
      (node (ref "U$3") (pin "14") (pinfunction "DB7_14") (pintype "bidirectional"))
    )
    (net (code "22") (name "LCD_ENABLE") (class "Default")
      (node (ref "IC4") (pin "38") (pinfunction "(ADC2)PA2_38") (pintype "bidirectional"))
      (node (ref "U$3") (pin "6") (pinfunction "E_6") (pintype "input"))
    )
    (net (code "23") (name "LCD_RS") (class "Default")
      (node (ref "IC4") (pin "37") (pinfunction "(ADC3)PA3_37") (pintype "bidirectional"))
      (node (ref "U$3") (pin "4") (pinfunction "RS_4") (pintype "input"))
    )
    (net (code "24") (name "MIDI_IN") (class "Default")
      (node (ref "IC4") (pin "14") (pinfunction "(RXD)PD0_14") (pintype "bidirectional"))
      (node (ref "OK1") (pin "6") (pinfunction "VO_6") (pintype "passive"))
      (node (ref "R5") (pin "1") (pinfunction "1_1") (pintype "passive"))
    )
    (net (code "25") (name "MISO") (class "Default")
      (node (ref "IC4") (pin "7") (pinfunction "(MISO)PB6_7") (pintype "bidirectional"))
      (node (ref "U1") (pin "1") (pinfunction "1_1") (pintype "passive"))
    )
    (net (code "26") (name "MOSI") (class "Default")
      (node (ref "IC3") (pin "4") (pinfunction "SDI_4") (pintype "input"))
      (node (ref "IC4") (pin "6") (pinfunction "(MOSI)PB5_6") (pintype "bidirectional"))
      (node (ref "U1") (pin "4") (pinfunction "4_4") (pintype "passive"))
    )
    (net (code "27") (name "Net-(C1-Pad2)") (class "Default")
      (node (ref "C1") (pin "2") (pinfunction "2_2") (pintype "passive"))
      (node (ref "J8") (pin "T") (pinfunction "T_T") (pintype "passive"))
      (node (ref "R1") (pin "2") (pinfunction "2_2") (pintype "passive"))
      (node (ref "R4") (pin "2") (pinfunction "2_2") (pintype "passive"))
    )
    (net (code "28") (name "Net-(C6-Pad-)") (class "Default")
      (node (ref "C6") (pin "-") (pinfunction "-_-") (pintype "passive"))
      (node (ref "R11") (pin "1") (pinfunction "1_1") (pintype "passive"))
    )
    (net (code "29") (name "Net-(C24-Pad-)") (class "Default")
      (node (ref "C24") (pin "-") (pinfunction "-_-") (pintype "passive"))
      (node (ref "R29") (pin "1") (pinfunction "1_1") (pintype "passive"))
    )
    (net (code "30") (name "Net-(IC2A--IN)") (class "Default")
      (node (ref "C1") (pin "1") (pinfunction "1_1") (pintype "passive"))
      (node (ref "IC2") (pin "2") (pinfunction "-IN_2") (pintype "input"))
      (node (ref "R4") (pin "1") (pinfunction "1_1") (pintype "passive"))
      (node (ref "R7") (pin "2") (pinfunction "2_2") (pintype "passive"))
    )
    (net (code "31") (name "Net-(IC2A-OUT)") (class "Default")
      (node (ref "IC2") (pin "1") (pinfunction "OUT_1") (pintype "output"))
      (node (ref "R1") (pin "1") (pinfunction "1_1") (pintype "passive"))
    )
    (net (code "32") (name "Net-(IC2B--IN)") (class "Default")
      (node (ref "C7") (pin "1") (pinfunction "1_1") (pintype "passive"))
      (node (ref "IC2") (pin "6") (pinfunction "-IN_6") (pintype "input"))
      (node (ref "R11") (pin "2") (pinfunction "2_2") (pintype "passive"))
      (node (ref "R15") (pin "1") (pinfunction "1_1") (pintype "passive"))
    )
    (net (code "33") (name "Net-(IC2B-OUT)") (class "Default")
      (node (ref "C7") (pin "2") (pinfunction "2_2") (pintype "passive"))
      (node (ref "IC2") (pin "7") (pinfunction "OUT_7") (pintype "output"))
      (node (ref "J4") (pin "TIP") (pinfunction "2_TIP") (pintype "passive"))
      (node (ref "R15") (pin "2") (pinfunction "2_2") (pintype "passive"))
    )
    (net (code "34") (name "Net-(IC2C--IN)") (class "Default")
      (node (ref "C8") (pin "1") (pinfunction "1_1") (pintype "passive"))
      (node (ref "IC2") (pin "9") (pinfunction "-IN_9") (pintype "input"))
      (node (ref "R10") (pin "2") (pinfunction "2_2") (pintype "passive"))
      (node (ref "R12") (pin "2") (pinfunction "2_2") (pintype "passive"))
      (node (ref "R16") (pin "1") (pinfunction "1_1") (pintype "passive"))
    )
    (net (code "35") (name "Net-(IC2C-OUT)") (class "Default")
      (node (ref "C8") (pin "2") (pinfunction "2_2") (pintype "passive"))
      (node (ref "IC2") (pin "8") (pinfunction "OUT_8") (pintype "output"))
      (node (ref "J3") (pin "TIP") (pinfunction "2_TIP") (pintype "passive"))
      (node (ref "R16") (pin "2") (pinfunction "2_2") (pintype "passive"))
    )
    (net (code "36") (name "Net-(IC2D--IN)") (class "Default")
      (node (ref "IC2") (pin "13") (pinfunction "-IN_13") (pintype "input"))
      (node (ref "IC2") (pin "14") (pinfunction "OUT_14") (pintype "output"))
    )
    (net (code "37") (name "Net-(IC4-AREF)") (class "Default")
      (node (ref "C18") (pin "1") (pinfunction "1_1") (pintype "passive"))
      (node (ref "IC4") (pin "32") (pinfunction "AREF_32") (pintype "passive"))
    )
    (net (code "38") (name "Net-(IC4-XTAL1)") (class "Default")
      (node (ref "C13") (pin "2") (pinfunction "2_2") (pintype "passive"))
      (node (ref "IC4") (pin "13") (pinfunction "XTAL1_13") (pintype "bidirectional"))
      (node (ref "Q2") (pin "1") (pinfunction "1_1") (pintype "passive"))
    )
    (net (code "39") (name "Net-(IC4-XTAL2)") (class "Default")
      (node (ref "C14") (pin "2") (pinfunction "2_2") (pintype "passive"))
      (node (ref "IC4") (pin "12") (pinfunction "XTAL2_12") (pintype "bidirectional"))
      (node (ref "Q2") (pin "2") (pinfunction "2_2") (pintype "passive"))
    )
    (net (code "40") (name "Net-(IC5A-QA)") (class "Default")
      (node (ref "IC5") (pin "15") (pinfunction "QA_15") (pintype "tri_state"))
      (node (ref "R19") (pin "1") (pinfunction "1_1") (pintype "passive"))
    )
    (net (code "41") (name "Net-(IC5A-QB)") (class "Default")
      (node (ref "IC5") (pin "1") (pinfunction "QB_1") (pintype "tri_state"))
      (node (ref "R20") (pin "1") (pinfunction "1_1") (pintype "passive"))
    )
    (net (code "42") (name "Net-(IC5A-QC)") (class "Default")
      (node (ref "IC5") (pin "2") (pinfunction "QC_2") (pintype "tri_state"))
      (node (ref "R21") (pin "1") (pinfunction "1_1") (pintype "passive"))
    )
    (net (code "43") (name "Net-(IC5A-QD)") (class "Default")
      (node (ref "IC5") (pin "3") (pinfunction "QD_3") (pintype "tri_state"))
      (node (ref "R22") (pin "1") (pinfunction "1_1") (pintype "passive"))
    )
    (net (code "44") (name "Net-(IC5A-QE)") (class "Default")
      (node (ref "IC5") (pin "4") (pinfunction "QE_4") (pintype "tri_state"))
      (node (ref "R23") (pin "1") (pinfunction "1_1") (pintype "passive"))
    )
    (net (code "45") (name "Net-(IC5A-QF)") (class "Default")
      (node (ref "IC5") (pin "5") (pinfunction "QF_5") (pintype "tri_state"))
      (node (ref "R24") (pin "1") (pinfunction "1_1") (pintype "passive"))
    )
    (net (code "46") (name "Net-(IC6A-A)") (class "Default")
      (node (ref "IC6") (pin "11") (pinfunction "A_11") (pintype "input"))
      (node (ref "RN1") (pin "7") (pinfunction "7_7") (pintype "passive"))
      (node (ref "S1") (pin "3") (pinfunction "P_3") (pintype "passive"))
      (node (ref "S1") (pin "4") (pinfunction "P1_4") (pintype "passive"))
    )
    (net (code "47") (name "Net-(IC6A-B)") (class "Default")
      (node (ref "IC6") (pin "12") (pinfunction "B_12") (pintype "input"))
      (node (ref "RN1") (pin "6") (pinfunction "6_6") (pintype "passive"))
      (node (ref "S2") (pin "3") (pinfunction "P_3") (pintype "passive"))
      (node (ref "S2") (pin "4") (pinfunction "P1_4") (pintype "passive"))
    )
    (net (code "48") (name "Net-(IC6A-C)") (class "Default")
      (node (ref "IC6") (pin "13") (pinfunction "C_13") (pintype "input"))
      (node (ref "RN1") (pin "5") (pinfunction "5_5") (pintype "passive"))
      (node (ref "S3") (pin "3") (pinfunction "P_3") (pintype "passive"))
      (node (ref "S3") (pin "4") (pinfunction "P1_4") (pintype "passive"))
    )
    (net (code "49") (name "Net-(IC6A-D)") (class "Default")
      (node (ref "IC6") (pin "14") (pinfunction "D_14") (pintype "input"))
      (node (ref "RN1") (pin "4") (pinfunction "4_4") (pintype "passive"))
      (node (ref "S4") (pin "3") (pinfunction "P_3") (pintype "passive"))
      (node (ref "S4") (pin "4") (pinfunction "P1_4") (pintype "passive"))
    )
    (net (code "50") (name "Net-(IC6A-E)") (class "Default")
      (node (ref "IC6") (pin "3") (pinfunction "E_3") (pintype "input"))
      (node (ref "RN1") (pin "3") (pinfunction "3_3") (pintype "passive"))
      (node (ref "S5") (pin "3") (pinfunction "P_3") (pintype "passive"))
      (node (ref "S5") (pin "4") (pinfunction "P1_4") (pintype "passive"))
    )
    (net (code "51") (name "Net-(IC6A-F)") (class "Default")
      (node (ref "IC6") (pin "4") (pinfunction "F_4") (pintype "input"))
      (node (ref "RN1") (pin "2") (pinfunction "2_2") (pintype "passive"))
      (node (ref "S6") (pin "3") (pinfunction "P_3") (pintype "passive"))
      (node (ref "S6") (pin "4") (pinfunction "P1_4") (pintype "passive"))
    )
    (net (code "52") (name "Net-(IC7A--IN)") (class "Default")
      (node (ref "IC7") (pin "2") (pinfunction "-IN_2") (pintype "input"))
      (node (ref "R30") (pin "1") (pinfunction "1_1") (pintype "passive"))
      (node (ref "R32") (pin "2") (pinfunction "2_2") (pintype "passive"))
    )
    (net (code "53") (name "Net-(IC7B-+IN)") (class "Default")
      (node (ref "C25") (pin "1") (pinfunction "1_1") (pintype "passive"))
      (node (ref "IC7") (pin "5") (pinfunction "+IN_5") (pintype "input"))
      (node (ref "R31") (pin "2") (pinfunction "2_2") (pintype "passive"))
      (node (ref "R33") (pin "1") (pinfunction "1_1") (pintype "passive"))
    )
    (net (code "54") (name "Net-(IC7B--IN)") (class "Default")
      (node (ref "C22") (pin "1") (pinfunction "1_1") (pintype "passive"))
      (node (ref "IC7") (pin "6") (pinfunction "-IN_6") (pintype "input"))
      (node (ref "R28") (pin "1") (pinfunction "1_1") (pintype "passive"))
      (node (ref "R29") (pin "2") (pinfunction "2_2") (pintype "passive"))
    )
    (net (code "55") (name "Net-(J1-2)") (class "Default")
      (node (ref "J1") (pin "TIP") (pinfunction "2_TIP") (pintype "passive"))
      (node (ref "R25") (pin "2") (pinfunction "2_2") (pintype "passive"))
    )
    (net (code "56") (name "Net-(J2-2)") (class "Default")
      (node (ref "J2") (pin "TIP") (pinfunction "2_TIP") (pintype "passive"))
      (node (ref "R27") (pin "2") (pinfunction "2_2") (pintype "passive"))
    )
    (net (code "57") (name "Net-(J5-2)") (class "Default")
      (node (ref "C24") (pin "+") (pinfunction "+_+") (pintype "passive"))
      (node (ref "J5") (pin "TIP") (pinfunction "2_TIP") (pintype "passive"))
      (node (ref "R32") (pin "1") (pinfunction "1_1") (pintype "passive"))
      (node (ref "R7") (pin "1") (pinfunction "1_1") (pintype "passive"))
    )
    (net (code "58") (name "Net-(J6-2)") (class "Default")
      (node (ref "J6") (pin "TIP") (pinfunction "2_TIP") (pintype "passive"))
      (node (ref "R18") (pin "1") (pinfunction "1_1") (pintype "passive"))
    )
    (net (code "59") (name "Net-(J10-1)") (class "Default")
      (node (ref "J10") (pin "GND") (pinfunction "1_GND") (pintype "passive"))
      (node (ref "J10") (pin "SW") (pinfunction "3_SW") (pintype "passive"))
      (node (ref "J7") (pin "5") (pinfunction "5_5") (pintype "passive"))
      (node (ref "J7") (pin "6") (pinfunction "6_6") (pintype "passive"))
    )
    (net (code "60") (name "Net-(J11-1)") (class "Default")
      (node (ref "J11") (pin "GND") (pinfunction "1_GND") (pintype "passive"))
      (node (ref "J11") (pin "SW") (pinfunction "3_SW") (pintype "passive"))
      (node (ref "J7") (pin "7") (pinfunction "7_7") (pintype "passive"))
      (node (ref "J7") (pin "8") (pinfunction "8_8") (pintype "passive"))
    )
    (net (code "61") (name "Net-(J12-1)") (class "Default")
      (node (ref "J12") (pin "GND") (pinfunction "1_GND") (pintype "passive"))
      (node (ref "J12") (pin "TIP") (pinfunction "2_TIP") (pintype "passive"))
      (node (ref "J7") (pin "15") (pinfunction "15_15") (pintype "passive"))
      (node (ref "J7") (pin "16") (pinfunction "16_16") (pintype "passive"))
    )
    (net (code "62") (name "Net-(LED1-PadA)") (class "Default")
      (node (ref "LED1") (pin "A") (pinfunction "A_A") (pintype "passive"))
      (node (ref "R19") (pin "2") (pinfunction "2_2") (pintype "passive"))
    )
    (net (code "63") (name "Net-(LED2-PadA)") (class "Default")
      (node (ref "LED2") (pin "A") (pinfunction "A_A") (pintype "passive"))
      (node (ref "R20") (pin "2") (pinfunction "2_2") (pintype "passive"))
    )
    (net (code "64") (name "Net-(LED3-PadA)") (class "Default")
      (node (ref "LED3") (pin "A") (pinfunction "A_A") (pintype "passive"))
      (node (ref "R21") (pin "2") (pinfunction "2_2") (pintype "passive"))
    )
    (net (code "65") (name "Net-(LED4-PadA)") (class "Default")
      (node (ref "LED4") (pin "A") (pinfunction "A_A") (pintype "passive"))
      (node (ref "R22") (pin "2") (pinfunction "2_2") (pintype "passive"))
    )
    (net (code "66") (name "Net-(LED5-PadA)") (class "Default")
      (node (ref "LED5") (pin "A") (pinfunction "A_A") (pintype "passive"))
      (node (ref "R23") (pin "2") (pinfunction "2_2") (pintype "passive"))
    )
    (net (code "67") (name "Net-(LED6-PadA)") (class "Default")
      (node (ref "LED6") (pin "A") (pinfunction "A_A") (pintype "passive"))
      (node (ref "R24") (pin "2") (pinfunction "2_2") (pintype "passive"))
    )
    (net (code "68") (name "Net-(OK1-A)") (class "Default")
      (node (ref "D1") (pin "C") (pinfunction "C_C") (pintype "passive"))
      (node (ref "OK1") (pin "2") (pinfunction "A_2") (pintype "passive"))
      (node (ref "R3") (pin "2") (pinfunction "2_2") (pintype "passive"))
    )
    (net (code "69") (name "Net-(OK1-C)") (class "Default")
      (node (ref "D1") (pin "A") (pinfunction "A_A") (pintype "passive"))
      (node (ref "OK1") (pin "3") (pinfunction "C_3") (pintype "passive"))
      (node (ref "X1") (pin "5") (pinfunction "5_5") (pintype "passive"))
    )
    (net (code "70") (name "Net-(Q1-B)") (class "Default")
      (node (ref "Q1") (pin "2") (pinfunction "B_2") (pintype "passive"))
      (node (ref "R18") (pin "2") (pinfunction "2_2") (pintype "passive"))
    )
    (net (code "71") (name "Net-(R3-Pad1)") (class "Default")
      (node (ref "R3") (pin "1") (pinfunction "1_1") (pintype "passive"))
      (node (ref "X1") (pin "4") (pinfunction "4_4") (pintype "passive"))
    )
    (net (code "72") (name "Net-(R8-S)") (class "Default")
      (node (ref "R8") (pin "2") (pinfunction "S_2") (pintype "passive"))
      (node (ref "U$3") (pin "3") (pinfunction "VO_3") (pintype "bidirectional"))
    )
    (net (code "73") (name "Net-(R9-E)") (class "Default")
      (node (ref "R6") (pin "1") (pinfunction "1_1") (pintype "passive"))
      (node (ref "R9") (pin "3") (pinfunction "E_3") (pintype "passive"))
    )
    (net (code "74") (name "Net-(R10-Pad1)") (class "Default")
      (node (ref "R10") (pin "1") (pinfunction "1_1") (pintype "passive"))
      (node (ref "R6") (pin "2") (pinfunction "2_2") (pintype "passive"))
    )
    (net (code "75") (name "Net-(R13-E)") (class "Default")
      (node (ref "R12") (pin "1") (pinfunction "1_1") (pintype "passive"))
      (node (ref "R13") (pin "3") (pinfunction "E_3") (pintype "passive"))
    )
    (net (code "76") (name "Net-(S7-O)") (class "Default")
      (node (ref "C10") (pin "+") (pinfunction "+_+") (pintype "passive"))
      (node (ref "S7") (pin "1") (pinfunction "O_1") (pintype "passive"))
      (node (ref "U$10") (pin "P$3") (pinfunction "VIN_P$3") (pintype "bidirectional"))
    )
    (net (code "77") (name "Net-(S7-P)") (class "Default")
      (node (ref "J9") (pin "3") (pinfunction "3_3") (pintype "passive"))
      (node (ref "S7") (pin "2") (pinfunction "P_2") (pintype "passive"))
    )
    (net (code "78") (name "Net-(U$3-A)") (class "Default")
      (node (ref "R14") (pin "2") (pinfunction "2_2") (pintype "passive"))
      (node (ref "U$3") (pin "15") (pinfunction "A_15") (pintype "power_in"))
    )
    (net (code "79") (name "PITCH_DETECTOR") (class "Default")
      (node (ref "IC4") (pin "20") (pinfunction "(ICP)PD6_20") (pintype "bidirectional"))
      (node (ref "IC7") (pin "1") (pinfunction "OUT_1") (pintype "output"))
      (node (ref "R30") (pin "2") (pinfunction "2_2") (pintype "passive"))
    )
    (net (code "80") (name "REF_-4.096") (class "Default")
      (node (ref "C3") (pin "1") (pinfunction "1_1") (pintype "passive"))
      (node (ref "IC1") (pin "3") (pinfunction "A_3") (pintype "passive"))
      (node (ref "R2") (pin "2") (pinfunction "2_2") (pintype "passive"))
      (node (ref "R9") (pin "1") (pinfunction "A_1") (pintype "passive"))
      (node (ref "R9") (pin "2") (pinfunction "S_2") (pintype "passive"))
    )
    (net (code "81") (name "RESET") (class "Default")
      (node (ref "C20") (pin "1") (pinfunction "1_1") (pintype "passive"))
      (node (ref "IC4") (pin "9") (pinfunction "RESET_9") (pintype "input"))
      (node (ref "R26") (pin "1") (pinfunction "1_1") (pintype "passive"))
      (node (ref "U1") (pin "5") (pinfunction "5_5") (pintype "passive"))
    )
    (net (code "82") (name "SCK") (class "Default")
      (node (ref "IC3") (pin "3") (pinfunction "SCK_3") (pintype "input"))
      (node (ref "IC4") (pin "8") (pinfunction "(SCK)PB7_8") (pintype "bidirectional"))
      (node (ref "U1") (pin "3") (pinfunction "3_3") (pintype "passive"))
    )
    (net (code "83") (name "SS") (class "Default")
      (node (ref "IC3") (pin "2") (pinfunction "#CS_2") (pintype "input"))
      (node (ref "IC4") (pin "5") (pinfunction "(SS)PB4_5") (pintype "bidirectional"))
    )
    (net (code "84") (name "VCC") (class "Default")
      (node (ref "C19") (pin "1") (pinfunction "1_1") (pintype "passive"))
      (node (ref "C27") (pin "+") (pinfunction "+_+") (pintype "passive"))
      (node (ref "C4") (pin "1") (pinfunction "1_1") (pintype "passive"))
      (node (ref "IC2") (pin "4") (pinfunction "V+_4") (pintype "power_in"))
      (node (ref "IC8") (pin "IN") (pinfunction "IN_IN") (pintype "input"))
      (node (ref "J11") (pin "TIP") (pinfunction "2_TIP") (pintype "passive"))
      (node (ref "U$10") (pin "P$6") (pinfunction "+VO_P$6") (pintype "bidirectional"))
    )
    (net (code "85") (name "VEE") (class "Default")
      (node (ref "C28") (pin "-") (pinfunction "-_-") (pintype "passive"))
      (node (ref "C5") (pin "2") (pinfunction "2_2") (pintype "passive"))
      (node (ref "IC2") (pin "11") (pinfunction "V-_11") (pintype "power_in"))
      (node (ref "J12") (pin "SW") (pinfunction "3_SW") (pintype "passive"))
      (node (ref "R2") (pin "1") (pinfunction "1_1") (pintype "passive"))
      (node (ref "U$10") (pin "P$4") (pinfunction "-VO_P$4") (pintype "bidirectional"))
    )
    (net (code "86") (name "unconnected-(IC4-(ADC1)PA1-Pad39)") (class "Default")
      (node (ref "IC4") (pin "39") (pinfunction "(ADC1)PA1_39") (pintype "bidirectional"))
    )
    (net (code "87") (name "unconnected-(IC4-(AIN0{slash}INT2)PB2-Pad3)") (class "Default")
      (node (ref "IC4") (pin "3") (pinfunction "(AIN0/INT2)PB2_3") (pintype "bidirectional"))
    )
    (net (code "88") (name "unconnected-(IC4-(AIN1{slash}OC0)PB3-Pad4)") (class "Default")
      (node (ref "IC4") (pin "4") (pinfunction "(AIN1/OC0)PB3_4") (pintype "bidirectional"))
    )
    (net (code "89") (name "unconnected-(IC4-(OC1A)PD5-Pad19)") (class "Default")
      (node (ref "IC4") (pin "19") (pinfunction "(OC1A)PD5_19") (pintype "bidirectional"))
    )
    (net (code "90") (name "unconnected-(IC4-(OC2)PD7-Pad21)") (class "Default")
      (node (ref "IC4") (pin "21") (pinfunction "(OC2)PD7_21") (pintype "bidirectional"))
    )
    (net (code "91") (name "unconnected-(IC4-(T0{slash}XCK)PB0-Pad1)") (class "Default")
      (node (ref "IC4") (pin "1") (pinfunction "(T0/XCK)PB0_1") (pintype "bidirectional"))
    )
    (net (code "92") (name "unconnected-(IC4-(T1)PB1-Pad2)") (class "Default")
      (node (ref "IC4") (pin "2") (pinfunction "(T1)PB1_2") (pintype "bidirectional"))
    )
    (net (code "93") (name "unconnected-(IC4-(TMS)PC3-Pad25)") (class "Default")
      (node (ref "IC4") (pin "25") (pinfunction "(TMS)PC3_25") (pintype "bidirectional"))
    )
    (net (code "94") (name "unconnected-(IC4-(TXD)PD1-Pad15)") (class "Default")
      (node (ref "IC4") (pin "15") (pinfunction "(TXD)PD1_15") (pintype "bidirectional"))
    )
    (net (code "95") (name "unconnected-(IC5A-QG-Pad6)") (class "Default")
      (node (ref "IC5") (pin "6") (pinfunction "QG_6") (pintype "tri_state"))
    )
    (net (code "96") (name "unconnected-(IC5A-QH*-Pad9)") (class "Default")
      (node (ref "IC5") (pin "9") (pinfunction "QH*_9") (pintype "tri_state"))
    )
    (net (code "97") (name "unconnected-(IC5A-QH-Pad7)") (class "Default")
      (node (ref "IC5") (pin "7") (pinfunction "QH_7") (pintype "tri_state"))
    )
    (net (code "98") (name "unconnected-(IC6A-~{QH}-Pad7)") (class "Default")
      (node (ref "IC6") (pin "7") (pinfunction "~{QH}_7") (pintype "output"))
    )
    (net (code "99") (name "unconnected-(J1-3-PadSW)") (class "Default")
      (node (ref "J1") (pin "SW") (pinfunction "3_SW") (pintype "passive"))
    )
    (net (code "100") (name "unconnected-(J2-3-PadSW)") (class "Default")
      (node (ref "J2") (pin "SW") (pinfunction "3_SW") (pintype "passive"))
    )
    (net (code "101") (name "unconnected-(J3-3-PadSW)") (class "Default")
      (node (ref "J3") (pin "SW") (pinfunction "3_SW") (pintype "passive"))
    )
    (net (code "102") (name "unconnected-(J4-3-PadSW)") (class "Default")
      (node (ref "J4") (pin "SW") (pinfunction "3_SW") (pintype "passive"))
    )
    (net (code "103") (name "unconnected-(J5-3-PadSW)") (class "Default")
      (node (ref "J5") (pin "SW") (pinfunction "3_SW") (pintype "passive"))
    )
    (net (code "104") (name "unconnected-(J7-Pad1)") (class "Default")
      (node (ref "J7") (pin "1") (pinfunction "1_1") (pintype "passive"))
    )
    (net (code "105") (name "unconnected-(J7-Pad2)") (class "Default")
      (node (ref "J7") (pin "2") (pinfunction "2_2") (pintype "passive"))
    )
    (net (code "106") (name "unconnected-(J7-Pad3)") (class "Default")
      (node (ref "J7") (pin "3") (pinfunction "3_3") (pintype "passive"))
    )
    (net (code "107") (name "unconnected-(J7-Pad4)") (class "Default")
      (node (ref "J7") (pin "4") (pinfunction "4_4") (pintype "passive"))
    )
    (net (code "108") (name "unconnected-(J8-PadTN)") (class "Default")
      (node (ref "J8") (pin "TN") (pinfunction "TN_TN") (pintype "passive"))
    )
    (net (code "109") (name "unconnected-(J9-Pad2)") (class "Default")
      (node (ref "J9") (pin "2") (pinfunction "2_2") (pintype "passive"))
    )
    (net (code "110") (name "unconnected-(J10-4-PadGND2)") (class "Default")
      (node (ref "J10") (pin "GND2") (pinfunction "4_GND2") (pintype "passive"))
    )
    (net (code "111") (name "unconnected-(J11-4-PadGND2)") (class "Default")
      (node (ref "J11") (pin "GND2") (pinfunction "4_GND2") (pintype "passive"))
    )
    (net (code "112") (name "unconnected-(J12-4-PadGND2)") (class "Default")
      (node (ref "J12") (pin "GND2") (pinfunction "4_GND2") (pintype "passive"))
    )
    (net (code "113") (name "unconnected-(OK1-VB-Pad7)") (class "Default")
      (node (ref "OK1") (pin "7") (pinfunction "VB_7") (pintype "passive"))
    )
    (net (code "114") (name "unconnected-(S7-S-Pad3)") (class "Default")
      (node (ref "S7") (pin "3") (pinfunction "S_3") (pintype "passive"))
    )
    (net (code "115") (name "unconnected-(U$3-DB0-Pad7)") (class "Default")
      (node (ref "U$3") (pin "7") (pinfunction "DB0_7") (pintype "bidirectional"))
    )
    (net (code "116") (name "unconnected-(U$3-DB1-Pad8)") (class "Default")
      (node (ref "U$3") (pin "8") (pinfunction "DB1_8") (pintype "bidirectional"))
    )
    (net (code "117") (name "unconnected-(U$3-DB2-Pad9)") (class "Default")
      (node (ref "U$3") (pin "9") (pinfunction "DB2_9") (pintype "bidirectional"))
    )
    (net (code "118") (name "unconnected-(U$3-DB3-Pad10)") (class "Default")
      (node (ref "U$3") (pin "10") (pinfunction "DB3_10") (pintype "bidirectional"))
    )
    (net (code "119") (name "unconnected-(U$10-CTRL-PadP$1)") (class "Default")
      (node (ref "U$10") (pin "P$1") (pinfunction "CTRL_P$1") (pintype "bidirectional"))
    )
    (net (code "120") (name "unconnected-(X1-Pad1)") (class "Default")
      (node (ref "X1") (pin "1") (pinfunction "1_1") (pintype "passive"))
    )
    (net (code "121") (name "unconnected-(X1-Pad2)") (class "Default")
      (node (ref "X1") (pin "2") (pinfunction "2_2") (pintype "passive"))
    )
    (net (code "122") (name "unconnected-(X1-Pad3)") (class "Default")
      (node (ref "X1") (pin "3") (pinfunction "3_3") (pintype "passive"))
    )
  )
)
